# Serial.net
KiCad netlist of a schematic drawn in Altium Designer
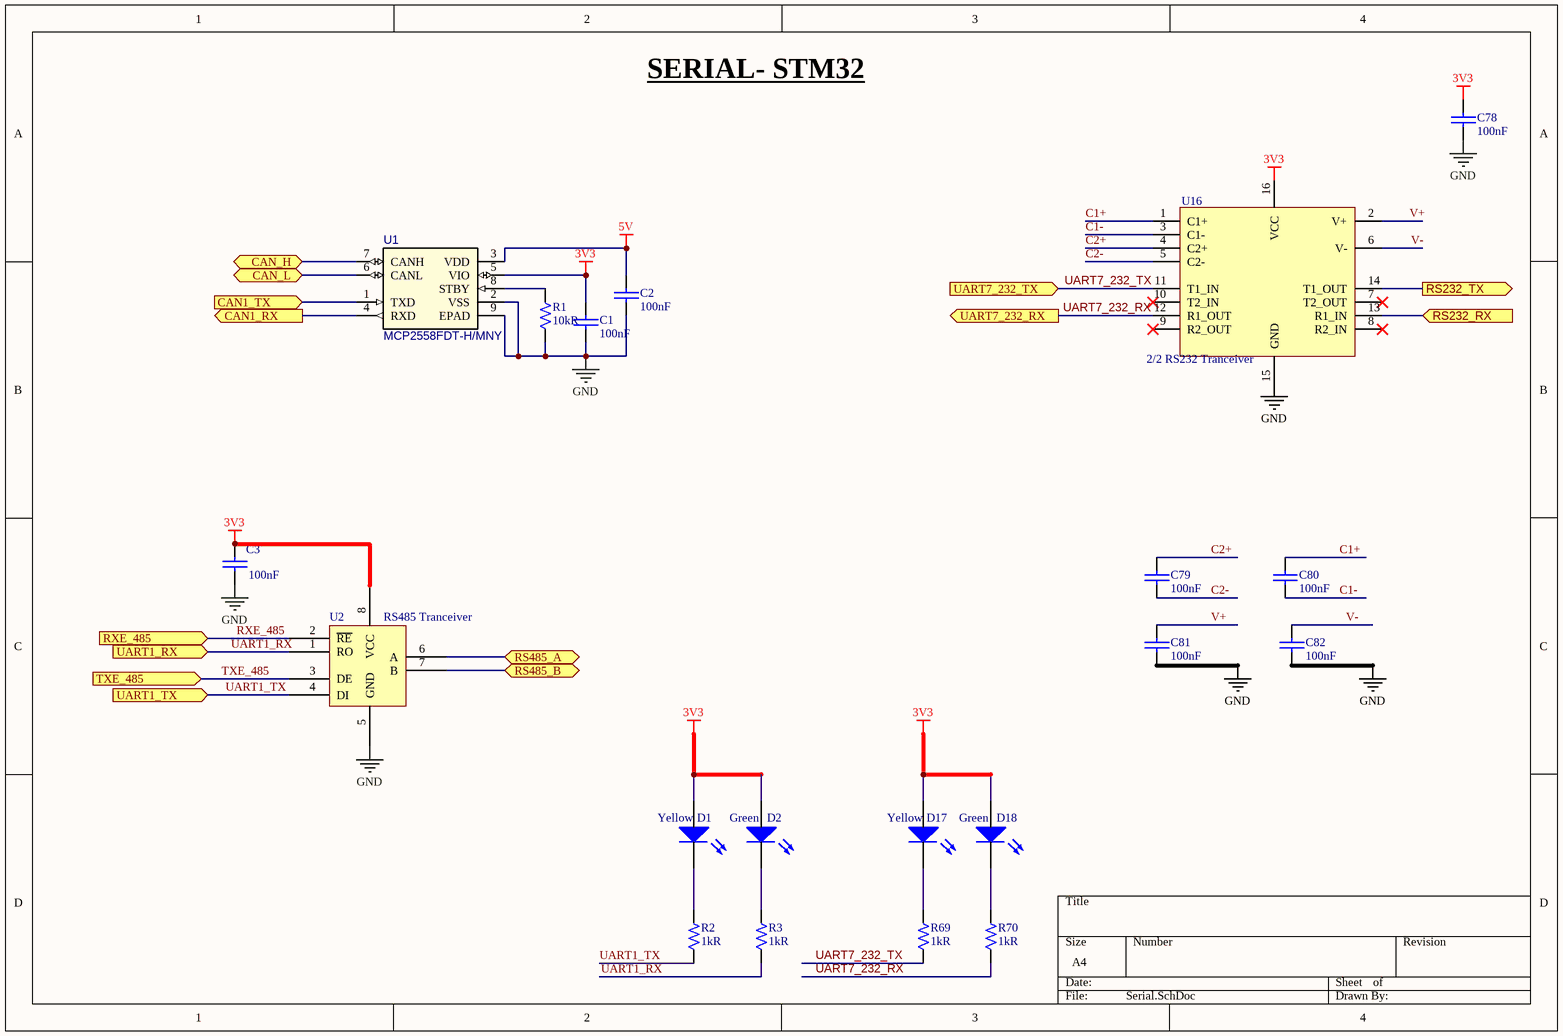
[diagram p0: Serial.SchDoc]

(export (version "E")
  (design (tool "Eeschema 10.0.6"))
  (components
    (comp (ref "C1")
      (value "Capacitor")
      (footprint "CAP0402")
      (fields
        (field (name "MANUFACTURER") "TDK")
        (field (name "MANUFACTURER PART NUMBER") "CGA2B3X7R1H104K050BB")
        (field (name "CAPACITANCE") "100nF")
        (field (name "TOLERANCE") "10%")
      )
      (libsource (lib "BPL-ShematicLibrary") (part "Capacitor"))
    )
    (comp (ref "C2")
      (value "Capacitor")
      (footprint "CAP0402")
      (fields
        (field (name "MANUFACTURER") "TDK")
        (field (name "MANUFACTURER PART NUMBER") "CGA2B3X7R1H104K050BB")
        (field (name "CAPACITANCE") "100nF")
        (field (name "TOLERANCE") "10%")
      )
      (libsource (lib "BPL-ShematicLibrary") (part "Capacitor"))
    )
    (comp (ref "C3")
      (value "Capacitor")
      (footprint "CAP0402")
      (fields
        (field (name "MANUFACTURER") "TDK")
        (field (name "MANUFACTURER PART NUMBER") "CGA2B3X7R1H104K050BB")
        (field (name "CAPACITANCE") "100nF")
        (field (name "TOLERANCE") "10%")
      )
      (libsource (lib "BPL-ShematicLibrary") (part "Capacitor"))
    )
    (comp (ref "C78")
      (value "Capacitor")
      (footprint "CAP0402")
      (fields
        (field (name "MANUFACTURER") "TDK")
        (field (name "MANUFACTURER PART NUMBER") "CGA2B3X7R1H104K050BB")
        (field (name "CAPACITANCE") "100nF")
        (field (name "TOLERANCE") "10%")
      )
      (libsource (lib "BPL-ShematicLibrary") (part "Capacitor"))
    )
    (comp (ref "C79")
      (value "Capacitor")
      (footprint "CAP0402")
      (fields
        (field (name "MANUFACTURER") "TDK")
        (field (name "MANUFACTURER PART NUMBER") "CGA2B3X7R1H104K050BB")
        (field (name "CAPACITANCE") "100nF")
        (field (name "TOLERANCE") "10%")
      )
      (libsource (lib "BPL-ShematicLibrary") (part "Capacitor"))
    )
    (comp (ref "C80")
      (value "Capacitor")
      (footprint "CAP0402")
      (fields
        (field (name "MANUFACTURER") "TDK")
        (field (name "MANUFACTURER PART NUMBER") "CGA2B3X7R1H104K050BB")
        (field (name "CAPACITANCE") "100nF")
        (field (name "TOLERANCE") "10%")
      )
      (libsource (lib "BPL-ShematicLibrary") (part "Capacitor"))
    )
    (comp (ref "C81")
      (value "Capacitor")
      (footprint "CAP0402")
      (fields
        (field (name "MANUFACTURER") "TDK")
        (field (name "MANUFACTURER PART NUMBER") "CGA2B3X7R1H104K050BB")
        (field (name "CAPACITANCE") "100nF")
        (field (name "TOLERANCE") "10%")
      )
      (libsource (lib "BPL-ShematicLibrary") (part "Capacitor"))
    )
    (comp (ref "C82")
      (value "Capacitor")
      (footprint "CAP0402")
      (fields
        (field (name "MANUFACTURER") "TDK")
        (field (name "MANUFACTURER PART NUMBER") "CGA2B3X7R1H104K050BB")
        (field (name "CAPACITANCE") "100nF")
        (field (name "TOLERANCE") "10%")
      )
      (libsource (lib "BPL-ShematicLibrary") (part "Capacitor"))
    )
    (comp (ref "D1")
      (value "LED")
      (footprint "LED-0603-YELLOW")
      (fields
        (field (name "MANUFACTURER") "Wurth Electronics Inc.")
        (field (name "MANUFACTURER PART NUMBER") "150060YS75000")
        (field (name "COLOUR") "Yellow")
      )
      (libsource (lib "BPL-ShematicLibrary") (part "LED"))
    )
    (comp (ref "D2")
      (value "LED")
      (footprint "LED-0603-GREEN")
      (fields
        (field (name "MANUFACTURER") "Wurth Electronics Inc.")
        (field (name "MANUFACTURER PART NUMBER") "150060GS75000")
        (field (name "COLOUR") "Green")
      )
      (libsource (lib "BPL-ShematicLibrary") (part "LED"))
    )
    (comp (ref "D17")
      (value "LED")
      (footprint "LED-0603-YELLOW")
      (fields
        (field (name "MANUFACTURER") "Wurth Electronics Inc.")
        (field (name "MANUFACTURER PART NUMBER") "150060YS75000")
        (field (name "COLOUR") "Yellow")
      )
      (libsource (lib "BPL-ShematicLibrary") (part "LED"))
    )
    (comp (ref "D18")
      (value "LED")
      (footprint "LED-0603-GREEN")
      (fields
        (field (name "MANUFACTURER") "Wurth Electronics Inc.")
        (field (name "MANUFACTURER PART NUMBER") "150060GS75000")
        (field (name "COLOUR") "Green")
      )
      (libsource (lib "BPL-ShematicLibrary") (part "LED"))
    )
    (comp (ref "R1")
      (value "Resistor")
      (footprint "RES0402")
      (fields (field (name "RESISTANCE") "10kR") (field (name "TOLERANCE") "1%"))
      (libsource (lib "BPL-ShematicLibrary") (part "Resistor"))
    )
    (comp (ref "R2")
      (value "Resistor")
      (footprint "RES0402")
      (fields (field (name "TOLERANCE") "5%") (field (name "RESISTANCE") "1kR"))
      (libsource (lib "BPL-ShematicLibrary") (part "Resistor"))
    )
    (comp (ref "R3")
      (value "Resistor")
      (footprint "RES0402")
      (fields (field (name "TOLERANCE") "5%") (field (name "RESISTANCE") "1kR"))
      (libsource (lib "BPL-ShematicLibrary") (part "Resistor"))
    )
    (comp (ref "R69")
      (value "Resistor")
      (footprint "RES0402")
      (fields (field (name "TOLERANCE") "5%") (field (name "RESISTANCE") "1kR"))
      (libsource (lib "BPL-ShematicLibrary") (part "Resistor"))
    )
    (comp (ref "R70")
      (value "Resistor")
      (footprint "RES0402")
      (fields (field (name "TOLERANCE") "5%") (field (name "RESISTANCE") "1kR"))
      (libsource (lib "BPL-ShematicLibrary") (part "Resistor"))
    )
    (comp (ref "U1")
      (value "MCP2558FDT-H/MNY")
      (footprint "TDFN8_2x3_MN")
      (description "Can Fd Transceiver With Silent Mode / 8 Tdfn 2X3X0.8Mm T/r")
      (fields (field (name "MANUFACTURER PART NUMBER 1") "MCP2558FDT-H/MNY"))
      (libsource (lib "BPL-ShematicLibrary") (part "MCP2558FDT-H/MNY"))
    )
    (comp (ref "U2")
      (value "RS485 Tranceiver")
      (footprint "MAX22501EATA+")
      (fields
        (field (name "MANUFACTURER PART NUMBER") "MAX22501EATA+")
        (field (name "MANUFACTURER") "Maxim Integrated")
      )
      (libsource (lib "BPL-ShematicLibrary") (part "MAX22501EATA+"))
    )
    (comp (ref "U16")
      (value "2/2 RS232 Tranceiver")
      (footprint "ST3232ECTR")
      (fields
        (field (name "MANUFACTURER") "STMicroelectronics")
        (field (name "MANUFACTURER PART NUMBER") "ST3232ECTR")
      )
      (libsource (lib "BPL-ShematicLibrary") (part "ST3232ECTR"))
    )
  )
  (nets
    (net (code "1") (name "/C1+") (class "Default")
      (node (ref "C80") (pin "1") (pinfunction "1_1") (pintype "passive"))
      (node (ref "U16") (pin "1") (pinfunction "C1+_1") (pintype "passive"))
    )
    (net (code "2") (name "/C1-") (class "Default")
      (node (ref "C80") (pin "2") (pinfunction "2_2") (pintype "passive"))
      (node (ref "U16") (pin "3") (pinfunction "C1-_3") (pintype "passive"))
    )
    (net (code "3") (name "/C2+") (class "Default")
      (node (ref "C79") (pin "1") (pinfunction "1_1") (pintype "passive"))
      (node (ref "U16") (pin "4") (pinfunction "C2+_4") (pintype "passive"))
    )
    (net (code "4") (name "/C2-") (class "Default")
      (node (ref "C79") (pin "2") (pinfunction "2_2") (pintype "passive"))
      (node (ref "U16") (pin "5") (pinfunction "C2-_5") (pintype "passive"))
    )
    (net (code "5") (name "/CAN1_RX") (class "Default")
      (node (ref "U1") (pin "4") (pinfunction "RXD_4") (pintype "output"))
    )
    (net (code "6") (name "/CAN1_TX") (class "Default")
      (node (ref "U1") (pin "1") (pinfunction "TXD_1") (pintype "input"))
    )
    (net (code "7") (name "/CAN_H") (class "Default")
      (node (ref "U1") (pin "7") (pinfunction "CANH_7") (pintype "bidirectional"))
    )
    (net (code "8") (name "/CAN_L") (class "Default")
      (node (ref "U1") (pin "6") (pinfunction "CANL_6") (pintype "bidirectional"))
    )
    (net (code "9") (name "/RS232_RX") (class "Default")
      (node (ref "U16") (pin "13") (pinfunction "R1_IN_13") (pintype "passive"))
    )
    (net (code "10") (name "/RS232_TX") (class "Default")
      (node (ref "U16") (pin "14") (pinfunction "T1_OUT_14") (pintype "passive"))
    )
    (net (code "11") (name "/RS485_A") (class "Default")
      (node (ref "U2") (pin "6") (pinfunction "A_6") (pintype "passive"))
    )
    (net (code "12") (name "/RS485_B") (class "Default")
      (node (ref "U2") (pin "7") (pinfunction "B_7") (pintype "passive"))
    )
    (net (code "13") (name "/RXE_485") (class "Default")
      (node (ref "U2") (pin "2") (pinfunction "~{RE}_2") (pintype "passive"))
    )
    (net (code "14") (name "/TXE_485") (class "Default")
      (node (ref "U2") (pin "3") (pinfunction "DE_3") (pintype "passive"))
    )
    (net (code "15") (name "/UART1_RX") (class "Default")
      (node (ref "R3") (pin "1") (pinfunction "1_1") (pintype "passive"))
      (node (ref "U2") (pin "1") (pinfunction "RO_1") (pintype "passive"))
    )
    (net (code "16") (name "/UART1_TX") (class "Default")
      (node (ref "R2") (pin "1") (pinfunction "1_1") (pintype "passive"))
      (node (ref "U2") (pin "4") (pinfunction "DI_4") (pintype "passive"))
    )
    (net (code "17") (name "/UART7_232_RX") (class "Default")
      (node (ref "R70") (pin "1") (pinfunction "1_1") (pintype "passive"))
      (node (ref "U16") (pin "12") (pinfunction "R1_OUT_12") (pintype "passive"))
    )
    (net (code "18") (name "/UART7_232_TX") (class "Default")
      (node (ref "R69") (pin "1") (pinfunction "1_1") (pintype "passive"))
      (node (ref "U16") (pin "11") (pinfunction "T1_IN_11") (pintype "passive"))
    )
    (net (code "19") (name "/V+") (class "Default")
      (node (ref "C81") (pin "1") (pinfunction "1_1") (pintype "passive"))
      (node (ref "U16") (pin "2") (pinfunction "V+_2") (pintype "passive"))
    )
    (net (code "20") (name "/V-") (class "Default")
      (node (ref "C82") (pin "1") (pinfunction "1_1") (pintype "passive"))
      (node (ref "U16") (pin "6") (pinfunction "V-_6") (pintype "passive"))
    )
    (net (code "21") (name "3V3") (class "Default")
      (node (ref "C1") (pin "1") (pinfunction "1_1") (pintype "passive"))
      (node (ref "C3") (pin "1") (pinfunction "1_1") (pintype "passive"))
      (node (ref "C78") (pin "1") (pinfunction "1_1") (pintype "passive"))
      (node (ref "D1") (pin "2") (pinfunction "2_2") (pintype "passive"))
      (node (ref "D17") (pin "2") (pinfunction "2_2") (pintype "passive"))
      (node (ref "D18") (pin "2") (pinfunction "2_2") (pintype "passive"))
      (node (ref "D2") (pin "2") (pinfunction "2_2") (pintype "passive"))
      (node (ref "U1") (pin "5") (pinfunction "VIO_5") (pintype "bidirectional"))
      (node (ref "U16") (pin "16") (pinfunction "VCC_16") (pintype "passive"))
      (node (ref "U2") (pin "8") (pinfunction "VCC_8") (pintype "passive"))
    )
    (net (code "22") (name "5V") (class "Default")
      (node (ref "C2") (pin "1") (pinfunction "1_1") (pintype "passive"))
      (node (ref "U1") (pin "3") (pinfunction "VDD_3") (pintype "power_in"))
    )
    (net (code "23") (name "GND") (class "Default")
      (node (ref "C1") (pin "2") (pinfunction "2_2") (pintype "passive"))
      (node (ref "C2") (pin "2") (pinfunction "2_2") (pintype "passive"))
      (node (ref "C3") (pin "2") (pinfunction "2_2") (pintype "passive"))
      (node (ref "C78") (pin "2") (pinfunction "2_2") (pintype "passive"))
      (node (ref "C81") (pin "2") (pinfunction "2_2") (pintype "passive"))
      (node (ref "C82") (pin "2") (pinfunction "2_2") (pintype "passive"))
      (node (ref "R1") (pin "1") (pinfunction "1_1") (pintype "passive"))
      (node (ref "U1") (pin "2") (pinfunction "VSS_2") (pintype "power_in"))
      (node (ref "U1") (pin "9") (pinfunction "EPAD_9") (pintype "passive"))
      (node (ref "U16") (pin "15") (pinfunction "GND_15") (pintype "passive"))
      (node (ref "U2") (pin "5") (pinfunction "GND_5") (pintype "passive"))
    )
    (net (code "24") (name "Net-(D1-Pad1)") (class "Default")
      (node (ref "D1") (pin "1") (pinfunction "1_1") (pintype "passive"))
      (node (ref "R2") (pin "2") (pinfunction "2_2") (pintype "passive"))
    )
    (net (code "25") (name "Net-(D2-Pad1)") (class "Default")
      (node (ref "D2") (pin "1") (pinfunction "1_1") (pintype "passive"))
      (node (ref "R3") (pin "2") (pinfunction "2_2") (pintype "passive"))
    )
    (net (code "26") (name "Net-(D17-Pad1)") (class "Default")
      (node (ref "D17") (pin "1") (pinfunction "1_1") (pintype "passive"))
      (node (ref "R69") (pin "2") (pinfunction "2_2") (pintype "passive"))
    )
    (net (code "27") (name "Net-(D18-Pad1)") (class "Default")
      (node (ref "D18") (pin "1") (pinfunction "1_1") (pintype "passive"))
      (node (ref "R70") (pin "2") (pinfunction "2_2") (pintype "passive"))
    )
    (net (code "28") (name "Net-(U1-STBY)") (class "Default")
      (node (ref "R1") (pin "2") (pinfunction "2_2") (pintype "passive"))
      (node (ref "U1") (pin "8") (pinfunction "STBY_8") (pintype "input"))
    )
    (net (code "29") (name "unconnected-(U16-R2_IN-Pad8)") (class "Default")
      (node (ref "U16") (pin "8") (pinfunction "R2_IN_8") (pintype "passive+no_connect"))
    )
    (net (code "30") (name "unconnected-(U16-R2_OUT-Pad9)") (class "Default")
      (node (ref "U16") (pin "9") (pinfunction "R2_OUT_9") (pintype "passive+no_connect"))
    )
    (net (code "31") (name "unconnected-(U16-T2_IN-Pad10)") (class "Default")
      (node (ref "U16") (pin "10") (pinfunction "T2_IN_10") (pintype "passive+no_connect"))
    )
    (net (code "32") (name "unconnected-(U16-T2_OUT-Pad7)") (class "Default")
      (node (ref "U16") (pin "7") (pinfunction "T2_OUT_7") (pintype "passive+no_connect"))
    )
  )
)
